# 3_Power_Supply.net
KiCad netlist of a schematic drawn in Altium Designer
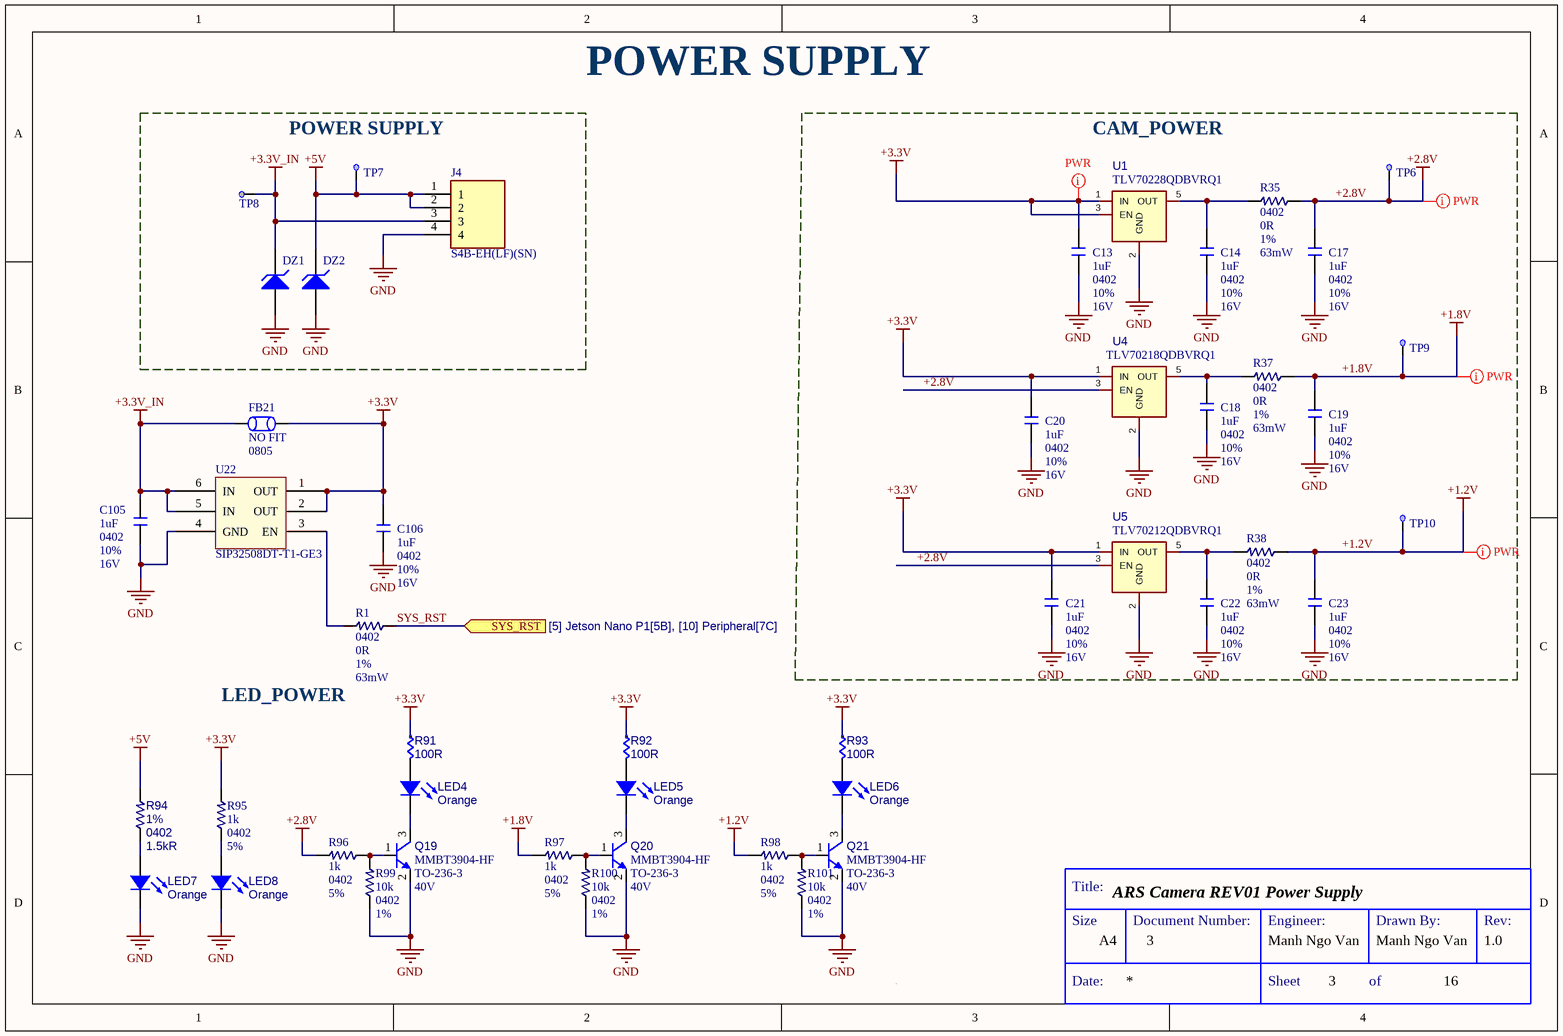
[diagram p0: [3] Power Supply.SchDoc]

(export (version "E")
  (design (tool "Eeschema 10.0.6"))
  (components
    (comp (ref "C13")
      (value "1uF")
      (footprint "C0402M")
      (fields
        (field (name "CASE CODE (IMPERIAL)") "0402")
        (field (name "TOLERANCE") "10%")
        (field (name "VOLTAGE") "16V")
      )
      (libsource (lib "CommonLib") (part "CAP_CER"))
    )
    (comp (ref "C14")
      (value "1uF")
      (footprint "C0402M")
      (fields
        (field (name "CASE CODE (IMPERIAL)") "0402")
        (field (name "TOLERANCE") "10%")
        (field (name "VOLTAGE") "16V")
      )
      (libsource (lib "CommonLib") (part "CAP_CER"))
    )
    (comp (ref "C17")
      (value "1uF")
      (footprint "C0402M")
      (fields
        (field (name "CASE CODE (IMPERIAL)") "0402")
        (field (name "TOLERANCE") "10%")
        (field (name "VOLTAGE") "16V")
      )
      (libsource (lib "CommonLib") (part "CAP_CER"))
    )
    (comp (ref "C18")
      (value "1uF")
      (footprint "C0402M")
      (fields
        (field (name "CASE CODE (IMPERIAL)") "0402")
        (field (name "TOLERANCE") "10%")
        (field (name "VOLTAGE") "16V")
      )
      (libsource (lib "CommonLib") (part "CAP_CER"))
    )
    (comp (ref "C19")
      (value "1uF")
      (footprint "C0402M")
      (fields
        (field (name "CASE CODE (IMPERIAL)") "0402")
        (field (name "TOLERANCE") "10%")
        (field (name "VOLTAGE") "16V")
      )
      (libsource (lib "CommonLib") (part "CAP_CER"))
    )
    (comp (ref "C20")
      (value "1uF")
      (footprint "C0402M")
      (fields
        (field (name "CASE CODE (IMPERIAL)") "0402")
        (field (name "TOLERANCE") "10%")
        (field (name "VOLTAGE") "16V")
      )
      (libsource (lib "CommonLib") (part "CAP_CER"))
    )
    (comp (ref "C21")
      (value "1uF")
      (footprint "C0402M")
      (fields
        (field (name "CASE CODE (IMPERIAL)") "0402")
        (field (name "TOLERANCE") "10%")
        (field (name "VOLTAGE") "16V")
      )
      (libsource (lib "CommonLib") (part "CAP_CER"))
    )
    (comp (ref "C22")
      (value "1uF")
      (footprint "C0402M")
      (fields
        (field (name "CASE CODE (IMPERIAL)") "0402")
        (field (name "TOLERANCE") "10%")
        (field (name "VOLTAGE") "16V")
      )
      (libsource (lib "CommonLib") (part "CAP_CER"))
    )
    (comp (ref "C23")
      (value "1uF")
      (footprint "C0402M")
      (fields
        (field (name "CASE CODE (IMPERIAL)") "0402")
        (field (name "TOLERANCE") "10%")
        (field (name "VOLTAGE") "16V")
      )
      (libsource (lib "CommonLib") (part "CAP_CER"))
    )
    (comp (ref "C105")
      (value "1uF")
      (footprint "C0402M")
      (fields
        (field (name "CASE CODE (IMPERIAL)") "0402")
        (field (name "TOLERANCE") "10%")
        (field (name "VOLTAGE") "16V")
      )
      (libsource (lib "CommonLib") (part "CAP_CER"))
    )
    (comp (ref "C106")
      (value "1uF")
      (footprint "C0402M")
      (fields
        (field (name "CASE CODE (IMPERIAL)") "0402")
        (field (name "TOLERANCE") "10%")
        (field (name "VOLTAGE") "16V")
      )
      (libsource (lib "CommonLib") (part "CAP_CER"))
    )
    (comp (ref "DZ1")
      (value "TPD1E10B06DPYR")
      (footprint "R0402M")
      (description "TVS DIODE 5.5V 14V 2X1SON")
      (fields (field (name "MANUFACTURER") "Texas Instruments"))
      (libsource (lib "CommonLib") (part "D Zener"))
    )
    (comp (ref "DZ2")
      (value "TPD1E10B06DPYR")
      (footprint "R0402M")
      (description "TVS DIODE 5.5V 14V 2X1SON")
      (fields (field (name "MANUFACTURER") "Texas Instruments"))
      (libsource (lib "CommonLib") (part "D Zener"))
    )
    (comp (ref "FB21")
      (value "NO FIT")
      (footprint "R0805M_NO_3D")
      (fields (field (name "CASE CODE (IMPERIAL)") "0805") (field (name "TOLERANCE") "25%"))
      (libsource (lib "CommonLib") (part "FB"))
    )
    (comp (ref "J4")
      (value "S4B-EH(LF)(SN)")
      (footprint "S4B-EH(LF)(SN)_1")
      (description "CONN HEADER R/A 4POS 2.5MM")
      (fields (field (name "MANUFACTURER") "JST"))
      (libsource (lib "GPS_DC_DC") (part "S4B-EH_LF__SN_"))
    )
    (comp (ref "LED4")
      (value "TLMO1000-GS08")
      (footprint "LED-0603 - TLMO1000-GS08")
      (description "LED ORANGE 0603 SMD")
      (fields (field (name "MANUFACTURER") "Vishay") (field (name "COLOR") "Orange"))
      (libsource (lib "3DAS_4Camera") (part "LED TLMO1000-GS08"))
    )
    (comp (ref "LED5")
      (value "TLMO1000-GS08")
      (footprint "LED-0603 - TLMO1000-GS08")
      (description "LED ORANGE 0603 SMD")
      (fields (field (name "MANUFACTURER") "Vishay") (field (name "COLOR") "Orange"))
      (libsource (lib "3DAS_4Camera") (part "LED TLMO1000-GS08"))
    )
    (comp (ref "LED6")
      (value "TLMO1000-GS08")
      (footprint "LED-0603 - TLMO1000-GS08")
      (description "LED ORANGE 0603 SMD")
      (fields (field (name "MANUFACTURER") "Vishay") (field (name "COLOR") "Orange"))
      (libsource (lib "3DAS_4Camera") (part "LED TLMO1000-GS08"))
    )
    (comp (ref "LED7")
      (value "TLMO1000-GS08")
      (footprint "LED-0603 - TLMO1000-GS08")
      (description "LED ORANGE 0603 SMD")
      (fields (field (name "MANUFACTURER") "Vishay") (field (name "COLOR") "Orange"))
      (libsource (lib "3DAS_4Camera") (part "LED TLMO1000-GS08"))
    )
    (comp (ref "LED8")
      (value "TLMO1000-GS08")
      (footprint "LED-0603 - TLMO1000-GS08")
      (description "LED ORANGE 0603 SMD")
      (fields (field (name "MANUFACTURER") "Vishay") (field (name "COLOR") "Orange"))
      (libsource (lib "3DAS_4Camera") (part "LED TLMO1000-GS08"))
    )
    (comp (ref "Q19")
      (value "NPN")
      (footprint "SOT55P160X90-3N")
      (description "TRANS NPN 40V 0.2A SOT523")
      (fields
        (field (name "MANUFACTURER PART NUMBER 1") "MMBT3904-HF")
        (field (name "CASE/PACKAGE") "TO-236-3")
        (field (name "COLLECTOR EMITTER BREAKDOWN VOLTAGE") "40V")
      )
      (libsource (lib "3DAS_4Camera") (part "NPN"))
    )
    (comp (ref "Q20")
      (value "NPN")
      (footprint "SOT55P160X90-3N")
      (description "TRANS NPN 40V 0.2A SOT523")
      (fields
        (field (name "MANUFACTURER PART NUMBER 1") "MMBT3904-HF")
        (field (name "CASE/PACKAGE") "TO-236-3")
        (field (name "COLLECTOR EMITTER BREAKDOWN VOLTAGE") "40V")
      )
      (libsource (lib "3DAS_4Camera") (part "NPN"))
    )
    (comp (ref "Q21")
      (value "NPN")
      (footprint "SOT55P160X90-3N")
      (description "TRANS NPN 40V 0.2A SOT523")
      (fields
        (field (name "MANUFACTURER PART NUMBER 1") "MMBT3904-HF")
        (field (name "CASE/PACKAGE") "TO-236-3")
        (field (name "COLLECTOR EMITTER BREAKDOWN VOLTAGE") "40V")
      )
      (libsource (lib "3DAS_4Camera") (part "NPN"))
    )
    (comp (ref "R1")
      (value "RC0402FR-070RL")
      (footprint "R0402M")
      (description "RC Series 0402 0.063 W 0 Ohm Jumper Surface Mount Thick Film Chip Resistor")
      (fields
        (field (name "CASE CODE (IMPERIAL)") "0402")
        (field (name "RESISTANCE") "0R")
        (field (name "TOLERANCE") "1%")
        (field (name "MAX POWER DISSIPATION") "63mW")
      )
      (libsource (lib "CommonLib") (part "RES_SMD"))
    )
    (comp (ref "R35")
      (value "RC0402FR-070RL")
      (footprint "R0402M")
      (description "RC Series 0402 0.063 W 0 Ohm Jumper Surface Mount Thick Film Chip Resistor")
      (fields
        (field (name "CASE CODE (IMPERIAL)") "0402")
        (field (name "RESISTANCE") "0R")
        (field (name "TOLERANCE") "1%")
        (field (name "MAX POWER DISSIPATION") "63mW")
      )
      (libsource (lib "CommonLib") (part "RES_SMD"))
    )
    (comp (ref "R37")
      (value "RC0402FR-070RL")
      (footprint "R0402M")
      (description "RC Series 0402 0.063 W 0 Ohm Jumper Surface Mount Thick Film Chip Resistor")
      (fields
        (field (name "CASE CODE (IMPERIAL)") "0402")
        (field (name "RESISTANCE") "0R")
        (field (name "TOLERANCE") "1%")
        (field (name "MAX POWER DISSIPATION") "63mW")
      )
      (libsource (lib "CommonLib") (part "RES_SMD"))
    )
    (comp (ref "R38")
      (value "RC0402FR-070RL")
      (footprint "R0402M")
      (description "RC Series 0402 0.063 W 0 Ohm Jumper Surface Mount Thick Film Chip Resistor")
      (fields
        (field (name "CASE CODE (IMPERIAL)") "0402")
        (field (name "RESISTANCE") "0R")
        (field (name "TOLERANCE") "1%")
        (field (name "MAX POWER DISSIPATION") "63mW")
      )
      (libsource (lib "CommonLib") (part "RES_SMD"))
    )
    (comp (ref "R91")
      (value "RC0603JR-07100RL")
      (footprint "RES0603")
      (description "RES SMD 100 OHM 5% 1/10W 0603")
      (fields (field (name "TOLERANCE") "5%") (field (name "RESISTANCE") "100R"))
      (libsource (lib "Altium Central") (part "=Resistance"))
    )
    (comp (ref "R92")
      (value "RC0603JR-07100RL")
      (footprint "RES0603")
      (description "RES SMD 100 OHM 5% 1/10W 0603")
      (fields (field (name "TOLERANCE") "5%") (field (name "RESISTANCE") "100R"))
      (libsource (lib "Altium Central") (part "=Resistance"))
    )
    (comp (ref "R93")
      (value "RC0603JR-07100RL")
      (footprint "RES0603")
      (description "RES SMD 100 OHM 5% 1/10W 0603")
      (fields (field (name "TOLERANCE") "5%") (field (name "RESISTANCE") "100R"))
      (libsource (lib "Altium Central") (part "=Resistance"))
    )
    (comp (ref "R94")
      (value "AC0402FR-071K5L")
      (footprint "R0402M")
      (description "RES SMD 1.5K OHM 1% 1/16W 0402")
      (fields
        (field (name "MANUFACTURER") "Yageo")
        (field (name "TOLERANCE") "1%")
        (field (name "CASE/PACKAGE") "0402")
        (field (name "RESISTANCE") "1.5kR")
      )
      (libsource (lib "3DAS_4Camera") (part "RES_SMD_1.5K"))
    )
    (comp (ref "R95")
      (value "1k")
      (footprint "R0402M")
      (description "RES SMD 1K OHM 5% 1/16W 0402")
      (fields
        (field (name "MANUFACTURER") "Yageo")
        (field (name "MANUFACTURER PART NUMBER") "RC0402JR-071KL")
        (field (name "CASE CODE (IMPERIAL)") "0402")
        (field (name "TOLERANCE") "5%")
      )
      (libsource (lib "CommonLib") (part "RES_SMD"))
    )
    (comp (ref "R96")
      (value "1k")
      (footprint "R0402M")
      (description "RES SMD 1K OHM 5% 1/16W 0402")
      (fields
        (field (name "MANUFACTURER") "Yageo")
        (field (name "MANUFACTURER PART NUMBER") "RC0402JR-071KL")
        (field (name "CASE CODE (IMPERIAL)") "0402")
        (field (name "TOLERANCE") "5%")
      )
      (libsource (lib "CommonLib") (part "RES_SMD"))
    )
    (comp (ref "R97")
      (value "1k")
      (footprint "R0402M")
      (description "RES SMD 1K OHM 5% 1/16W 0402")
      (fields
        (field (name "MANUFACTURER") "Yageo")
        (field (name "MANUFACTURER PART NUMBER") "RC0402JR-071KL")
        (field (name "CASE CODE (IMPERIAL)") "0402")
        (field (name "TOLERANCE") "5%")
      )
      (libsource (lib "CommonLib") (part "RES_SMD"))
    )
    (comp (ref "R98")
      (value "1k")
      (footprint "R0402M")
      (description "RES SMD 1K OHM 5% 1/16W 0402")
      (fields
        (field (name "MANUFACTURER") "Yageo")
        (field (name "MANUFACTURER PART NUMBER") "RC0402JR-071KL")
        (field (name "CASE CODE (IMPERIAL)") "0402")
        (field (name "TOLERANCE") "5%")
      )
      (libsource (lib "CommonLib") (part "RES_SMD"))
    )
    (comp (ref "R99")
      (value "10k")
      (footprint "R0402M")
      (description "RES SMD 10K OHM 1% 1/16W 0402")
      (fields
        (field (name "MANUFACTURER") "Yageo")
        (field (name "MANUFACTURER PART NUMBER") "RC0402FR-0710KL")
        (field (name "CASE CODE (IMPERIAL)") "0402")
        (field (name "TOLERANCE") "1%")
      )
      (libsource (lib "CommonLib") (part "RES_SMD"))
    )
    (comp (ref "R100")
      (value "10k")
      (footprint "R0402M")
      (description "RES SMD 10K OHM 1% 1/16W 0402")
      (fields
        (field (name "MANUFACTURER") "Yageo")
        (field (name "MANUFACTURER PART NUMBER") "RC0402FR-0710KL")
        (field (name "CASE CODE (IMPERIAL)") "0402")
        (field (name "TOLERANCE") "1%")
      )
      (libsource (lib "CommonLib") (part "RES_SMD"))
    )
    (comp (ref "R101")
      (value "10k")
      (footprint "R0402M")
      (description "RES SMD 10K OHM 1% 1/16W 0402")
      (fields
        (field (name "MANUFACTURER") "Yageo")
        (field (name "MANUFACTURER PART NUMBER") "RC0402FR-0710KL")
        (field (name "CASE CODE (IMPERIAL)") "0402")
        (field (name "TOLERANCE") "1%")
      )
      (libsource (lib "CommonLib") (part "RES_SMD"))
    )
    (comp (ref "TP6")
      (value "TP")
      (footprint "Test point")
      (description "TESTPOINT")
      (libsource (lib "CommonLib") (part "TestPoint"))
    )
    (comp (ref "TP7")
      (value "TP")
      (footprint "Test point")
      (description "TESTPOINT")
      (libsource (lib "CommonLib") (part "TestPoint"))
    )
    (comp (ref "TP8")
      (value "TP")
      (footprint "Test point")
      (description "TESTPOINT")
      (libsource (lib "CommonLib") (part "TestPoint"))
    )
    (comp (ref "TP9")
      (value "TP")
      (footprint "Test point")
      (description "TESTPOINT")
      (libsource (lib "CommonLib") (part "TestPoint"))
    )
    (comp (ref "TP10")
      (value "TP")
      (footprint "Test point")
      (description "TESTPOINT")
      (libsource (lib "CommonLib") (part "TestPoint"))
    )
    (comp (ref "U1")
      (value "TLV70228QDBVRQ1")
      (footprint "SOT95P280X145-5N")
      (description "LDO Regulator Pos 2.8V 0.3A Automotive 5-Pin SOT-23 T/R")
      (libsource (lib "Schlib1") (part "TLV70228QDBVRQ1"))
    )
    (comp (ref "U4")
      (value "TLV70218QDBVRQ1")
      (footprint "SOT95P280X145-5N")
      (description "LDO Regulator Pos 1.8V 0.3A Automotive 5-Pin SOT-23 T/R")
      (libsource (lib "Schlib1") (part "TLV70218QDBVRQ1"))
    )
    (comp (ref "U5")
      (value "TLV70212QDBVRQ1")
      (footprint "SOT95P280X145-5N")
      (description "LDO Regulator Pos 1.2V 0.3A Automotive 5-Pin SOT-23 T/R")
      (libsource (lib "Schlib1") (part "TLV70212QDBVRQ1"))
    )
    (comp (ref "U22")
      (value "SIP32508DT-T1-GE3")
      (footprint "SOT95P280X100-6N")
      (description "Power Switch ICs - Power Distribution Slew Rate Controlled Load Switch")
      (libsource (lib "tsynth_library") (part "SIP32508DT-T1-GE3"))
    )
  )
  (nets
    (net (code "1") (name "+1.2V") (class "Default")
      (node (ref "C23") (pin "1") (pinfunction "1_1") (pintype "passive"))
      (node (ref "R38") (pin "2") (pinfunction "2_2") (pintype "passive"))
      (node (ref "R98") (pin "1") (pinfunction "1_1") (pintype "passive"))
      (node (ref "TP10") (pin "1") (pinfunction "TP_1") (pintype "passive"))
    )
    (net (code "2") (name "+1.8V") (class "Default")
      (node (ref "C19") (pin "1") (pinfunction "1_1") (pintype "passive"))
      (node (ref "R37") (pin "2") (pinfunction "2_2") (pintype "passive"))
      (node (ref "R97") (pin "1") (pinfunction "1_1") (pintype "passive"))
      (node (ref "TP9") (pin "1") (pinfunction "TP_1") (pintype "passive"))
    )
    (net (code "3") (name "+2.8V") (class "Default")
      (node (ref "C17") (pin "1") (pinfunction "1_1") (pintype "passive"))
      (node (ref "R35") (pin "2") (pinfunction "2_2") (pintype "passive"))
      (node (ref "R96") (pin "1") (pinfunction "1_1") (pintype "passive"))
      (node (ref "TP6") (pin "1") (pinfunction "TP_1") (pintype "passive"))
      (node (ref "U4") (pin "3") (pinfunction "EN_3") (pintype "passive"))
      (node (ref "U5") (pin "3") (pinfunction "EN_3") (pintype "passive"))
    )
    (net (code "4") (name "+3.3V") (class "Default")
      (node (ref "C106") (pin "1") (pinfunction "1_1") (pintype "passive"))
      (node (ref "C13") (pin "1") (pinfunction "1_1") (pintype "passive"))
      (node (ref "C20") (pin "1") (pinfunction "1_1") (pintype "passive"))
      (node (ref "C21") (pin "1") (pinfunction "1_1") (pintype "passive"))
      (node (ref "FB21") (pin "1") (pinfunction "1_1") (pintype "passive"))
      (node (ref "R91") (pin "1") (pinfunction "1_1") (pintype "passive"))
      (node (ref "R92") (pin "1") (pinfunction "1_1") (pintype "passive"))
      (node (ref "R93") (pin "1") (pinfunction "1_1") (pintype "passive"))
      (node (ref "R95") (pin "1") (pinfunction "1_1") (pintype "passive"))
      (node (ref "U1") (pin "1") (pinfunction "IN_1") (pintype "passive"))
      (node (ref "U1") (pin "3") (pinfunction "EN_3") (pintype "passive"))
      (node (ref "U22") (pin "1") (pinfunction "OUT_1") (pintype "passive"))
      (node (ref "U22") (pin "2") (pinfunction "OUT_2") (pintype "passive"))
      (node (ref "U4") (pin "1") (pinfunction "IN_1") (pintype "passive"))
      (node (ref "U5") (pin "1") (pinfunction "IN_1") (pintype "passive"))
    )
    (net (code "5") (name "+3.3V_IN") (class "Default")
      (node (ref "C105") (pin "1") (pinfunction "1_1") (pintype "passive"))
      (node (ref "DZ1") (pin "2") (pinfunction "K_2") (pintype "passive"))
      (node (ref "FB21") (pin "2") (pinfunction "2_2") (pintype "passive"))
      (node (ref "J4") (pin "3") (pinfunction "3_3") (pintype "passive"))
      (node (ref "TP8") (pin "1") (pinfunction "TP_1") (pintype "passive"))
      (node (ref "U22") (pin "5") (pinfunction "IN_5") (pintype "passive"))
      (node (ref "U22") (pin "6") (pinfunction "IN_6") (pintype "passive"))
    )
    (net (code "6") (name "+5V") (class "Default")
      (node (ref "DZ2") (pin "2") (pinfunction "K_2") (pintype "passive"))
      (node (ref "J4") (pin "1") (pinfunction "1_1") (pintype "passive"))
      (node (ref "J4") (pin "2") (pinfunction "2_2") (pintype "passive"))
      (node (ref "R94") (pin "1") (pinfunction "1_1") (pintype "passive"))
      (node (ref "TP7") (pin "1") (pinfunction "TP_1") (pintype "passive"))
    )
    (net (code "7") (name "/SYS_RST") (class "Default")
      (node (ref "R1") (pin "2") (pinfunction "2_2") (pintype "passive"))
    )
    (net (code "8") (name "GND") (class "Default")
      (node (ref "C105") (pin "2") (pinfunction "2_2") (pintype "passive"))
      (node (ref "C106") (pin "2") (pinfunction "2_2") (pintype "passive"))
      (node (ref "C13") (pin "2") (pinfunction "2_2") (pintype "passive"))
      (node (ref "C14") (pin "2") (pinfunction "2_2") (pintype "passive"))
      (node (ref "C17") (pin "2") (pinfunction "2_2") (pintype "passive"))
      (node (ref "C18") (pin "2") (pinfunction "2_2") (pintype "passive"))
      (node (ref "C19") (pin "2") (pinfunction "2_2") (pintype "passive"))
      (node (ref "C20") (pin "2") (pinfunction "2_2") (pintype "passive"))
      (node (ref "C21") (pin "2") (pinfunction "2_2") (pintype "passive"))
      (node (ref "C22") (pin "2") (pinfunction "2_2") (pintype "passive"))
      (node (ref "C23") (pin "2") (pinfunction "2_2") (pintype "passive"))
      (node (ref "DZ1") (pin "1") (pinfunction "A_1") (pintype "passive"))
      (node (ref "DZ2") (pin "1") (pinfunction "A_1") (pintype "passive"))
      (node (ref "J4") (pin "4") (pinfunction "4_4") (pintype "passive"))
      (node (ref "LED7") (pin "2") (pinfunction "K_2") (pintype "passive"))
      (node (ref "LED8") (pin "2") (pinfunction "K_2") (pintype "passive"))
      (node (ref "Q19") (pin "2") (pinfunction "E_2") (pintype "passive"))
      (node (ref "Q20") (pin "2") (pinfunction "E_2") (pintype "passive"))
      (node (ref "Q21") (pin "2") (pinfunction "E_2") (pintype "passive"))
      (node (ref "R100") (pin "2") (pinfunction "2_2") (pintype "passive"))
      (node (ref "R101") (pin "2") (pinfunction "2_2") (pintype "passive"))
      (node (ref "R99") (pin "2") (pinfunction "2_2") (pintype "passive"))
      (node (ref "U1") (pin "2") (pinfunction "GND_2") (pintype "passive"))
      (node (ref "U22") (pin "4") (pinfunction "GND_4") (pintype "passive"))
      (node (ref "U4") (pin "2") (pinfunction "GND_2") (pintype "passive"))
      (node (ref "U5") (pin "2") (pinfunction "GND_2") (pintype "passive"))
    )
    (net (code "9") (name "Net-(LED4-A)") (class "Default")
      (node (ref "LED4") (pin "1") (pinfunction "A_1") (pintype "passive"))
      (node (ref "R91") (pin "2") (pinfunction "2_2") (pintype "passive"))
    )
    (net (code "10") (name "Net-(LED4-K)") (class "Default")
      (node (ref "LED4") (pin "2") (pinfunction "K_2") (pintype "passive"))
      (node (ref "Q19") (pin "3") (pinfunction "C_3") (pintype "passive"))
    )
    (net (code "11") (name "Net-(LED5-A)") (class "Default")
      (node (ref "LED5") (pin "1") (pinfunction "A_1") (pintype "passive"))
      (node (ref "R92") (pin "2") (pinfunction "2_2") (pintype "passive"))
    )
    (net (code "12") (name "Net-(LED5-K)") (class "Default")
      (node (ref "LED5") (pin "2") (pinfunction "K_2") (pintype "passive"))
      (node (ref "Q20") (pin "3") (pinfunction "C_3") (pintype "passive"))
    )
    (net (code "13") (name "Net-(LED6-A)") (class "Default")
      (node (ref "LED6") (pin "1") (pinfunction "A_1") (pintype "passive"))
      (node (ref "R93") (pin "2") (pinfunction "2_2") (pintype "passive"))
    )
    (net (code "14") (name "Net-(LED6-K)") (class "Default")
      (node (ref "LED6") (pin "2") (pinfunction "K_2") (pintype "passive"))
      (node (ref "Q21") (pin "3") (pinfunction "C_3") (pintype "passive"))
    )
    (net (code "15") (name "Net-(LED7-A)") (class "Default")
      (node (ref "LED7") (pin "1") (pinfunction "A_1") (pintype "passive"))
      (node (ref "R94") (pin "2") (pinfunction "2_2") (pintype "passive"))
    )
    (net (code "16") (name "Net-(LED8-A)") (class "Default")
      (node (ref "LED8") (pin "1") (pinfunction "A_1") (pintype "passive"))
      (node (ref "R95") (pin "2") (pinfunction "2_2") (pintype "passive"))
    )
    (net (code "17") (name "Net-(Q19-B)") (class "Default")
      (node (ref "Q19") (pin "1") (pinfunction "B_1") (pintype "passive"))
      (node (ref "R96") (pin "2") (pinfunction "2_2") (pintype "passive"))
      (node (ref "R99") (pin "1") (pinfunction "1_1") (pintype "passive"))
    )
    (net (code "18") (name "Net-(Q20-B)") (class "Default")
      (node (ref "Q20") (pin "1") (pinfunction "B_1") (pintype "passive"))
      (node (ref "R100") (pin "1") (pinfunction "1_1") (pintype "passive"))
      (node (ref "R97") (pin "2") (pinfunction "2_2") (pintype "passive"))
    )
    (net (code "19") (name "Net-(Q21-B)") (class "Default")
      (node (ref "Q21") (pin "1") (pinfunction "B_1") (pintype "passive"))
      (node (ref "R101") (pin "1") (pinfunction "1_1") (pintype "passive"))
      (node (ref "R98") (pin "2") (pinfunction "2_2") (pintype "passive"))
    )
    (net (code "20") (name "Net-(U1-OUT)") (class "Default")
      (node (ref "C14") (pin "1") (pinfunction "1_1") (pintype "passive"))
      (node (ref "R35") (pin "1") (pinfunction "1_1") (pintype "passive"))
      (node (ref "U1") (pin "5") (pinfunction "OUT_5") (pintype "passive"))
    )
    (net (code "21") (name "Net-(U4-OUT)") (class "Default")
      (node (ref "C18") (pin "1") (pinfunction "1_1") (pintype "passive"))
      (node (ref "R37") (pin "1") (pinfunction "1_1") (pintype "passive"))
      (node (ref "U4") (pin "5") (pinfunction "OUT_5") (pintype "passive"))
    )
    (net (code "22") (name "Net-(U5-OUT)") (class "Default")
      (node (ref "C22") (pin "1") (pinfunction "1_1") (pintype "passive"))
      (node (ref "R38") (pin "1") (pinfunction "1_1") (pintype "passive"))
      (node (ref "U5") (pin "5") (pinfunction "OUT_5") (pintype "passive"))
    )
    (net (code "23") (name "Net-(U22-EN)") (class "Default")
      (node (ref "R1") (pin "1") (pinfunction "1_1") (pintype "passive"))
      (node (ref "U22") (pin "3") (pinfunction "EN_3") (pintype "passive"))
    )
    (net (code "24") (name "unconnected-(U1-NC-Pad4)") (class "Default")
      (node (ref "U1") (pin "4") (pinfunction "NC_4") (pintype "passive"))
    )
    (net (code "25") (name "unconnected-(U4-NC-Pad4)") (class "Default")
      (node (ref "U4") (pin "4") (pinfunction "NC_4") (pintype "passive"))
    )
    (net (code "26") (name "unconnected-(U5-NC-Pad4)") (class "Default")
      (node (ref "U5") (pin "4") (pinfunction "NC_4") (pintype "passive"))
    )
  )
)
